# Sheet_Main.net
KiCad netlist of a schematic drawn in Altium Designer
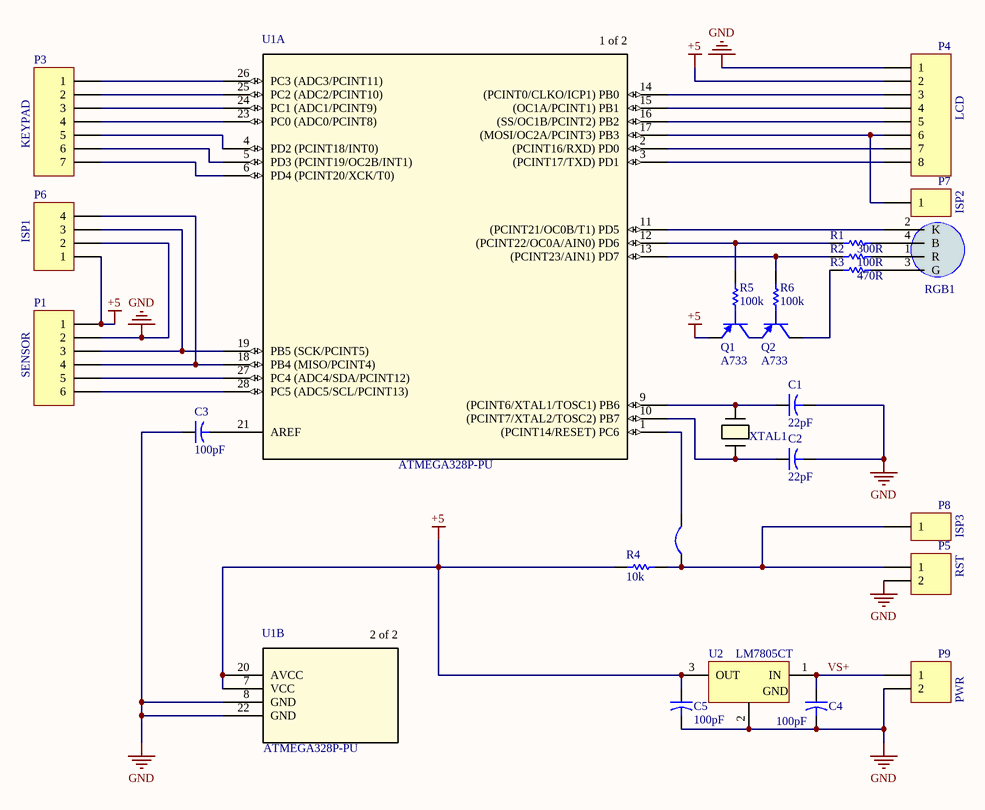
[diagram p0: Sheet_Main.SchDoc]

(export (version "E")
  (design (tool "Eeschema 10.0.6"))
  (components
    (comp (ref "*") (value "Jumper3") (footprint "JUMPER3") (libsource (lib "Common Parts") (part "Jumper3")))
    (comp (ref "C1")
      (value "22pF")
      (footprint "CAP3")
      (description "Capacitor")
      (fields (field (name "PUBLISHER") "Altium Limited"))
      (libsource (lib "Common Parts") (part "Cap1"))
    )
    (comp (ref "C2")
      (value "22pF")
      (footprint "CAP3")
      (description "Capacitor")
      (fields (field (name "PUBLISHER") "Altium Limited"))
      (libsource (lib "Common Parts") (part "Cap1"))
    )
    (comp (ref "C3")
      (value "100pF")
      (footprint "CAP3")
      (description "Capacitor")
      (fields (field (name "PUBLISHER") "Altium Limited"))
      (libsource (lib "Common Parts") (part "Cap1"))
    )
    (comp (ref "C4")
      (value "100pF")
      (footprint "CAP3")
      (description "Capacitor")
      (fields (field (name "PUBLISHER") "Altium Limited"))
      (libsource (lib "") (part "Cap1_1"))
    )
    (comp (ref "C5")
      (value "100pF")
      (footprint "CAP3")
      (description "Capacitor")
      (fields (field (name "PUBLISHER") "Altium Limited"))
      (libsource (lib "") (part "Cap1_1"))
    )
    (comp (ref "P1")
      (value "SENSOR")
      (footprint "H6")
      (description "Header, 6-Pin")
      (fields (field (name "PUBLISHER") "Altium Limited"))
      (libsource (lib "Miscellaneous Connectors") (part "Header 6"))
    )
    (comp (ref "P3")
      (value "KEYPAD")
      (footprint "H7")
      (description "Header, 7-Pin")
      (fields (field (name "PUBLISHER") "Altium Limited"))
      (libsource (lib "Miscellaneous Connectors") (part "Header 7"))
    )
    (comp (ref "P4")
      (value "LCD")
      (footprint "H8")
      (description "Header, 8-Pin")
      (fields (field (name "PUBLISHER") "Altium Limited"))
      (libsource (lib "Miscellaneous Connectors") (part "Header 8"))
    )
    (comp (ref "P5")
      (value "RST")
      (footprint "H2")
      (description "Header, 2-Pin")
      (fields (field (name "PUBLISHER") "Altium Limited"))
      (libsource (lib "Miscellaneous Connectors") (part "Header 2"))
    )
    (comp (ref "P6")
      (value "ISP1")
      (footprint "H4")
      (description "Header, 4-Pin")
      (fields (field (name "PUBLISHER") "Altium Limited"))
      (libsource (lib "Miscellaneous Connectors") (part "Header 4"))
    )
    (comp (ref "P7")
      (value "ISP2")
      (footprint "H1")
      (description "Header, 1-Pin")
      (fields (field (name "PUBLISHER") "Altium Limited"))
      (libsource (lib "Footprints_lib") (part "Header 1"))
    )
    (comp (ref "P8")
      (value "ISP3")
      (footprint "H1")
      (description "Header, 1-Pin")
      (fields (field (name "PUBLISHER") "Altium Limited"))
      (libsource (lib "Footprints_lib") (part "Header 1"))
    )
    (comp (ref "P9")
      (value "PWR")
      (footprint "H2_PWR")
      (description "Header, 2-Pin")
      (fields (field (name "PUBLISHER") "Altium Limited"))
      (libsource (lib "Footprints_lib") (part "Header 2"))
    )
    (comp (ref "Q1")
      (value "A733")
      (footprint "TO-92_ONS")
      (description "PNP General Purpose Transistor")
      (fields (field (name "PUBLISHER") "Altium Limited"))
      (libsource (lib "Common Parts") (part "A733"))
    )
    (comp (ref "Q2")
      (value "A733")
      (footprint "TO-92_ONS")
      (description "PNP General Purpose Transistor")
      (fields (field (name "PUBLISHER") "Altium Limited"))
      (libsource (lib "Common Parts") (part "A733"))
    )
    (comp (ref "R1")
      (value "300R")
      (footprint "RES")
      (description "Resistor")
      (fields (field (name "PUBLISHER") "Altium Limited"))
      (libsource (lib "Miscellaneous Devices") (part "Res1"))
    )
    (comp (ref "R2")
      (value "100R")
      (footprint "RES")
      (description "Resistor")
      (fields (field (name "PUBLISHER") "Altium Limited"))
      (libsource (lib "Miscellaneous Devices") (part "Res1"))
    )
    (comp (ref "R3")
      (value "470R")
      (footprint "RES")
      (description "Resistor")
      (fields (field (name "PUBLISHER") "Altium Limited"))
      (libsource (lib "Miscellaneous Devices") (part "Res1"))
    )
    (comp (ref "R4")
      (value "10k")
      (footprint "RES")
      (description "Resistor")
      (fields (field (name "PUBLISHER") "Altium Limited"))
      (libsource (lib "Common Parts") (part "Res1"))
    )
    (comp (ref "R5")
      (value "100k")
      (footprint "RES")
      (description "Resistor")
      (fields (field (name "PUBLISHER") "Altium Limited"))
      (libsource (lib "Miscellaneous Devices") (part "Res1"))
    )
    (comp (ref "R6")
      (value "100k")
      (footprint "RES")
      (description "Resistor")
      (fields (field (name "PUBLISHER") "Altium Limited"))
      (libsource (lib "Miscellaneous Devices") (part "Res1"))
    )
    (comp (ref "RGB1") (value "RGB") (footprint "H4") (libsource (lib "Common Parts") (part "RGB")))
    (comp (ref "U1")
      (value "ATMEGA328P-PU")
      (footprint "28P3_ATM")
      (description "No Description Available")
      (fields (field (name "COPYRIGHT") "Copyright (C) 2018 Accelerated Designs. All rights reserved"))
      (libsource (lib "ul_ATMEGA328PPU") (part "ATMEGA328P-PU"))
    )
    (comp (ref "U2")
      (value "LM7805CT")
      (footprint "FAIR-TO-220-3")
      (description "Positive Voltage Regulator, 5 V, 1 A, -40 to 125 degC, 3-Pin TO-220, RoHS, Tube")
      (fields (field (name "MANUFACTURER") "FairchildSemiconductor"))
      (libsource (lib "Altium Content Vault") (part "FAIR-LM7805CT-TO220-3"))
    )
    (comp (ref "XTAL1")
      (value "9B-11.0592MAAJ-B")
      (footprint "XTAL")
      (description "No Description Available")
      (fields (field (name "COPYRIGHT") "Copyright (C) 2018 Accelerated Designs. All rights reserved"))
      (libsource (lib "Footprints_lib") (part "9B-11.0592MAAJ-B"))
    )
  )
  (nets
    (net (code "1") (name "+5") (class "Default")
      (node (ref "C5") (pin "1") (pinfunction "1_1") (pintype "passive"))
      (node (ref "P1") (pin "1") (pinfunction "1_1") (pintype "passive"))
      (node (ref "P4") (pin "2") (pinfunction "2_2") (pintype "passive"))
      (node (ref "P6") (pin "1") (pinfunction "1_1") (pintype "passive"))
      (node (ref "Q1") (pin "1") (pinfunction "E_1") (pintype "passive"))
      (node (ref "R4") (pin "2") (pinfunction "2_2") (pintype "passive"))
      (node (ref "U1") (pin "20") (pinfunction "AVCC_20") (pintype "power_in"))
      (node (ref "U1") (pin "7") (pinfunction "VCC_7") (pintype "power_in"))
      (node (ref "U2") (pin "3") (pinfunction "OUT_3") (pintype "power_in"))
    )
    (net (code "2") (name "/VS+") (class "Default")
      (node (ref "C4") (pin "1") (pinfunction "1_1") (pintype "passive"))
      (node (ref "P9") (pin "1") (pinfunction "1_1") (pintype "passive"))
      (node (ref "U2") (pin "1") (pinfunction "IN_1") (pintype "power_in"))
    )
    (net (code "3") (name "GND") (class "Default")
      (node (ref "C1") (pin "2") (pinfunction "2_2") (pintype "passive"))
      (node (ref "C2") (pin "2") (pinfunction "2_2") (pintype "passive"))
      (node (ref "C3") (pin "1") (pinfunction "1_1") (pintype "passive"))
      (node (ref "C4") (pin "2") (pinfunction "2_2") (pintype "passive"))
      (node (ref "C5") (pin "2") (pinfunction "2_2") (pintype "passive"))
      (node (ref "P1") (pin "2") (pinfunction "2_2") (pintype "passive"))
      (node (ref "P4") (pin "1") (pinfunction "1_1") (pintype "passive"))
      (node (ref "P5") (pin "2") (pinfunction "2_2") (pintype "passive"))
      (node (ref "P6") (pin "2") (pinfunction "2_2") (pintype "passive"))
      (node (ref "P9") (pin "2") (pinfunction "2_2") (pintype "passive"))
      (node (ref "U1") (pin "22") (pinfunction "GND_22") (pintype "power_in"))
      (node (ref "U1") (pin "8") (pinfunction "GND_8") (pintype "power_in"))
      (node (ref "U2") (pin "2") (pinfunction "GND_2") (pintype "power_in"))
    )
    (net (code "4") (name "Net-(*-Pad1)") (class "Default")
      (node (ref "*") (pin "1") (pinfunction "1_1") (pintype "passive"))
      (node (ref "P5") (pin "1") (pinfunction "1_1") (pintype "passive"))
      (node (ref "P8") (pin "1") (pinfunction "1_1") (pintype "passive"))
      (node (ref "R4") (pin "1") (pinfunction "1_1") (pintype "passive"))
    )
    (net (code "5") (name "Net-(Q1-B)") (class "Default")
      (node (ref "Q1") (pin "3") (pinfunction "B_3") (pintype "passive"))
      (node (ref "R5") (pin "1") (pinfunction "1_1") (pintype "passive"))
    )
    (net (code "6") (name "Net-(Q1-C)") (class "Default")
      (node (ref "Q1") (pin "2") (pinfunction "C_2") (pintype "passive"))
      (node (ref "Q2") (pin "1") (pinfunction "E_1") (pintype "passive"))
    )
    (net (code "7") (name "Net-(Q2-B)") (class "Default")
      (node (ref "Q2") (pin "3") (pinfunction "B_3") (pintype "passive"))
      (node (ref "R6") (pin "1") (pinfunction "1_1") (pintype "passive"))
    )
    (net (code "8") (name "Net-(Q2-C)") (class "Default")
      (node (ref "Q2") (pin "2") (pinfunction "C_2") (pintype "passive"))
      (node (ref "R3") (pin "1") (pinfunction "1_1") (pintype "passive"))
    )
    (net (code "9") (name "Net-(RGB1-B)") (class "Default")
      (node (ref "R1") (pin "2") (pinfunction "2_2") (pintype "passive"))
      (node (ref "RGB1") (pin "4") (pinfunction "B_4") (pintype "passive"))
    )
    (net (code "10") (name "Net-(RGB1-G)") (class "Default")
      (node (ref "R3") (pin "2") (pinfunction "2_2") (pintype "passive"))
      (node (ref "RGB1") (pin "3") (pinfunction "G_3") (pintype "passive"))
    )
    (net (code "11") (name "Net-(RGB1-K)") (class "Default")
      (node (ref "RGB1") (pin "2") (pinfunction "K_2") (pintype "passive"))
      (node (ref "U1") (pin "11") (pinfunction "(PCINT21/OC0B/T1)_PD5_11") (pintype "bidirectional"))
    )
    (net (code "12") (name "Net-(RGB1-R)") (class "Default")
      (node (ref "R2") (pin "2") (pinfunction "2_2") (pintype "passive"))
      (node (ref "RGB1") (pin "1") (pinfunction "R_1") (pintype "passive"))
    )
    (net (code "13") (name "Net-(U1A-(MOSI{slash}OC2A{slash}PCINT3)_PB3)") (class "Default")
      (node (ref "P4") (pin "6") (pinfunction "6_6") (pintype "passive"))
      (node (ref "P7") (pin "1") (pinfunction "1_1") (pintype "passive"))
      (node (ref "U1") (pin "17") (pinfunction "(MOSI/OC2A/PCINT3)_PB3_17") (pintype "bidirectional"))
    )
    (net (code "14") (name "Net-(U1A-(OC1A{slash}PCINT1)_PB1)") (class "Default")
      (node (ref "P4") (pin "4") (pinfunction "4_4") (pintype "passive"))
      (node (ref "U1") (pin "15") (pinfunction "(OC1A/PCINT1)_PB1_15") (pintype "bidirectional"))
    )
    (net (code "15") (name "Net-(U1A-(PCINT0{slash}CLKO{slash}ICP1)_PB0)") (class "Default")
      (node (ref "P4") (pin "3") (pinfunction "3_3") (pintype "passive"))
      (node (ref "U1") (pin "14") (pinfunction "(PCINT0/CLKO/ICP1)_PB0_14") (pintype "bidirectional"))
    )
    (net (code "16") (name "Net-(U1A-(PCINT6{slash}XTAL1{slash}TOSC1)_PB6)") (class "Default")
      (node (ref "C1") (pin "1") (pinfunction "1_1") (pintype "passive"))
      (node (ref "U1") (pin "9") (pinfunction "(PCINT6/XTAL1/TOSC1)_PB6_9") (pintype "bidirectional"))
      (node (ref "XTAL1") (pin "1") (pinfunction "1_1") (pintype "passive"))
    )
    (net (code "17") (name "Net-(U1A-(PCINT7{slash}XTAL2{slash}TOSC2)_PB7)") (class "Default")
      (node (ref "C2") (pin "1") (pinfunction "1_1") (pintype "passive"))
      (node (ref "U1") (pin "10") (pinfunction "(PCINT7/XTAL2/TOSC2)_PB7_10") (pintype "bidirectional"))
      (node (ref "XTAL1") (pin "2") (pinfunction "2_2") (pintype "passive"))
    )
    (net (code "18") (name "Net-(U1A-(PCINT14{slash}RESET)_PC6)") (class "Default")
      (node (ref "*") (pin "2") (pinfunction "2_2") (pintype "passive"))
      (node (ref "U1") (pin "1") (pinfunction "(PCINT14/RESET)_PC6_1") (pintype "bidirectional"))
    )
    (net (code "19") (name "Net-(U1A-(PCINT16{slash}RXD)_PD0)") (class "Default")
      (node (ref "P4") (pin "7") (pinfunction "7_7") (pintype "passive"))
      (node (ref "U1") (pin "2") (pinfunction "(PCINT16/RXD)_PD0_2") (pintype "bidirectional"))
    )
    (net (code "20") (name "Net-(U1A-(PCINT17{slash}TXD)_PD1)") (class "Default")
      (node (ref "P4") (pin "8") (pinfunction "8_8") (pintype "passive"))
      (node (ref "U1") (pin "3") (pinfunction "(PCINT17/TXD)_PD1_3") (pintype "bidirectional"))
    )
    (net (code "21") (name "Net-(U1A-(PCINT22{slash}OC0A{slash}AIN0)_PD6)") (class "Default")
      (node (ref "R1") (pin "1") (pinfunction "1_1") (pintype "passive"))
      (node (ref "R5") (pin "2") (pinfunction "2_2") (pintype "passive"))
      (node (ref "U1") (pin "12") (pinfunction "(PCINT22/OC0A/AIN0)_PD6_12") (pintype "bidirectional"))
    )
    (net (code "22") (name "Net-(U1A-(PCINT23{slash}AIN1)_PD7)") (class "Default")
      (node (ref "R2") (pin "1") (pinfunction "1_1") (pintype "passive"))
      (node (ref "R6") (pin "2") (pinfunction "2_2") (pintype "passive"))
      (node (ref "U1") (pin "13") (pinfunction "(PCINT23/AIN1)_PD7_13") (pintype "bidirectional"))
    )
    (net (code "23") (name "Net-(U1A-(SS{slash}OC1B{slash}PCINT2)_PB2)") (class "Default")
      (node (ref "P4") (pin "5") (pinfunction "5_5") (pintype "passive"))
      (node (ref "U1") (pin "16") (pinfunction "(SS/OC1B/PCINT2)_PB2_16") (pintype "bidirectional"))
    )
    (net (code "24") (name "Net-(U1A-AREF)") (class "Default")
      (node (ref "C3") (pin "2") (pinfunction "2_2") (pintype "passive"))
      (node (ref "U1") (pin "21") (pinfunction "AREF_21") (pintype "passive"))
    )
    (net (code "25") (name "Net-(U1A-PB4_(MISO{slash}PCINT4))") (class "Default")
      (node (ref "P1") (pin "4") (pinfunction "4_4") (pintype "passive"))
      (node (ref "P6") (pin "4") (pinfunction "4_4") (pintype "passive"))
      (node (ref "U1") (pin "18") (pinfunction "PB4_(MISO/PCINT4)_18") (pintype "bidirectional"))
    )
    (net (code "26") (name "Net-(U1A-PB5_(SCK{slash}PCINT5))") (class "Default")
      (node (ref "P1") (pin "3") (pinfunction "3_3") (pintype "passive"))
      (node (ref "P6") (pin "3") (pinfunction "3_3") (pintype "passive"))
      (node (ref "U1") (pin "19") (pinfunction "PB5_(SCK/PCINT5)_19") (pintype "bidirectional"))
    )
    (net (code "27") (name "Net-(U1A-PC0_(ADC0{slash}PCINT8))") (class "Default")
      (node (ref "P3") (pin "4") (pinfunction "4_4") (pintype "passive"))
      (node (ref "U1") (pin "23") (pinfunction "PC0_(ADC0/PCINT8)_23") (pintype "bidirectional"))
    )
    (net (code "28") (name "Net-(U1A-PC1_(ADC1{slash}PCINT9))") (class "Default")
      (node (ref "P3") (pin "3") (pinfunction "3_3") (pintype "passive"))
      (node (ref "U1") (pin "24") (pinfunction "PC1_(ADC1/PCINT9)_24") (pintype "bidirectional"))
    )
    (net (code "29") (name "Net-(U1A-PC2_(ADC2{slash}PCINT10))") (class "Default")
      (node (ref "P3") (pin "2") (pinfunction "2_2") (pintype "passive"))
      (node (ref "U1") (pin "25") (pinfunction "PC2_(ADC2/PCINT10)_25") (pintype "bidirectional"))
    )
    (net (code "30") (name "Net-(U1A-PC3_(ADC3{slash}PCINT11))") (class "Default")
      (node (ref "P3") (pin "1") (pinfunction "1_1") (pintype "passive"))
      (node (ref "U1") (pin "26") (pinfunction "PC3_(ADC3/PCINT11)_26") (pintype "bidirectional"))
    )
    (net (code "31") (name "Net-(U1A-PC4_(ADC4{slash}SDA{slash}PCINT12))") (class "Default")
      (node (ref "P1") (pin "5") (pinfunction "5_5") (pintype "passive"))
      (node (ref "U1") (pin "27") (pinfunction "PC4_(ADC4/SDA/PCINT12)_27") (pintype "bidirectional"))
    )
    (net (code "32") (name "Net-(U1A-PC5_(ADC5{slash}SCL{slash}PCINT13))") (class "Default")
      (node (ref "P1") (pin "6") (pinfunction "6_6") (pintype "passive"))
      (node (ref "U1") (pin "28") (pinfunction "PC5_(ADC5/SCL/PCINT13)_28") (pintype "bidirectional"))
    )
    (net (code "33") (name "Net-(U1A-PD2_(PCINT18{slash}INT0))") (class "Default")
      (node (ref "P3") (pin "5") (pinfunction "5_5") (pintype "passive"))
      (node (ref "U1") (pin "4") (pinfunction "PD2_(PCINT18/INT0)_4") (pintype "bidirectional"))
    )
    (net (code "34") (name "Net-(U1A-PD3_(PCINT19{slash}OC2B{slash}INT1))") (class "Default")
      (node (ref "P3") (pin "6") (pinfunction "6_6") (pintype "passive"))
      (node (ref "U1") (pin "5") (pinfunction "PD3_(PCINT19/OC2B/INT1)_5") (pintype "bidirectional"))
    )
    (net (code "35") (name "Net-(U1A-PD4_(PCINT20{slash}XCK{slash}T0))") (class "Default")
      (node (ref "P3") (pin "7") (pinfunction "7_7") (pintype "passive"))
      (node (ref "U1") (pin "6") (pinfunction "PD4_(PCINT20/XCK/T0)_6") (pintype "bidirectional"))
    )
  )
)
